# RFID_R1.net
KiCad netlist of a schematic drawn in EAGLE
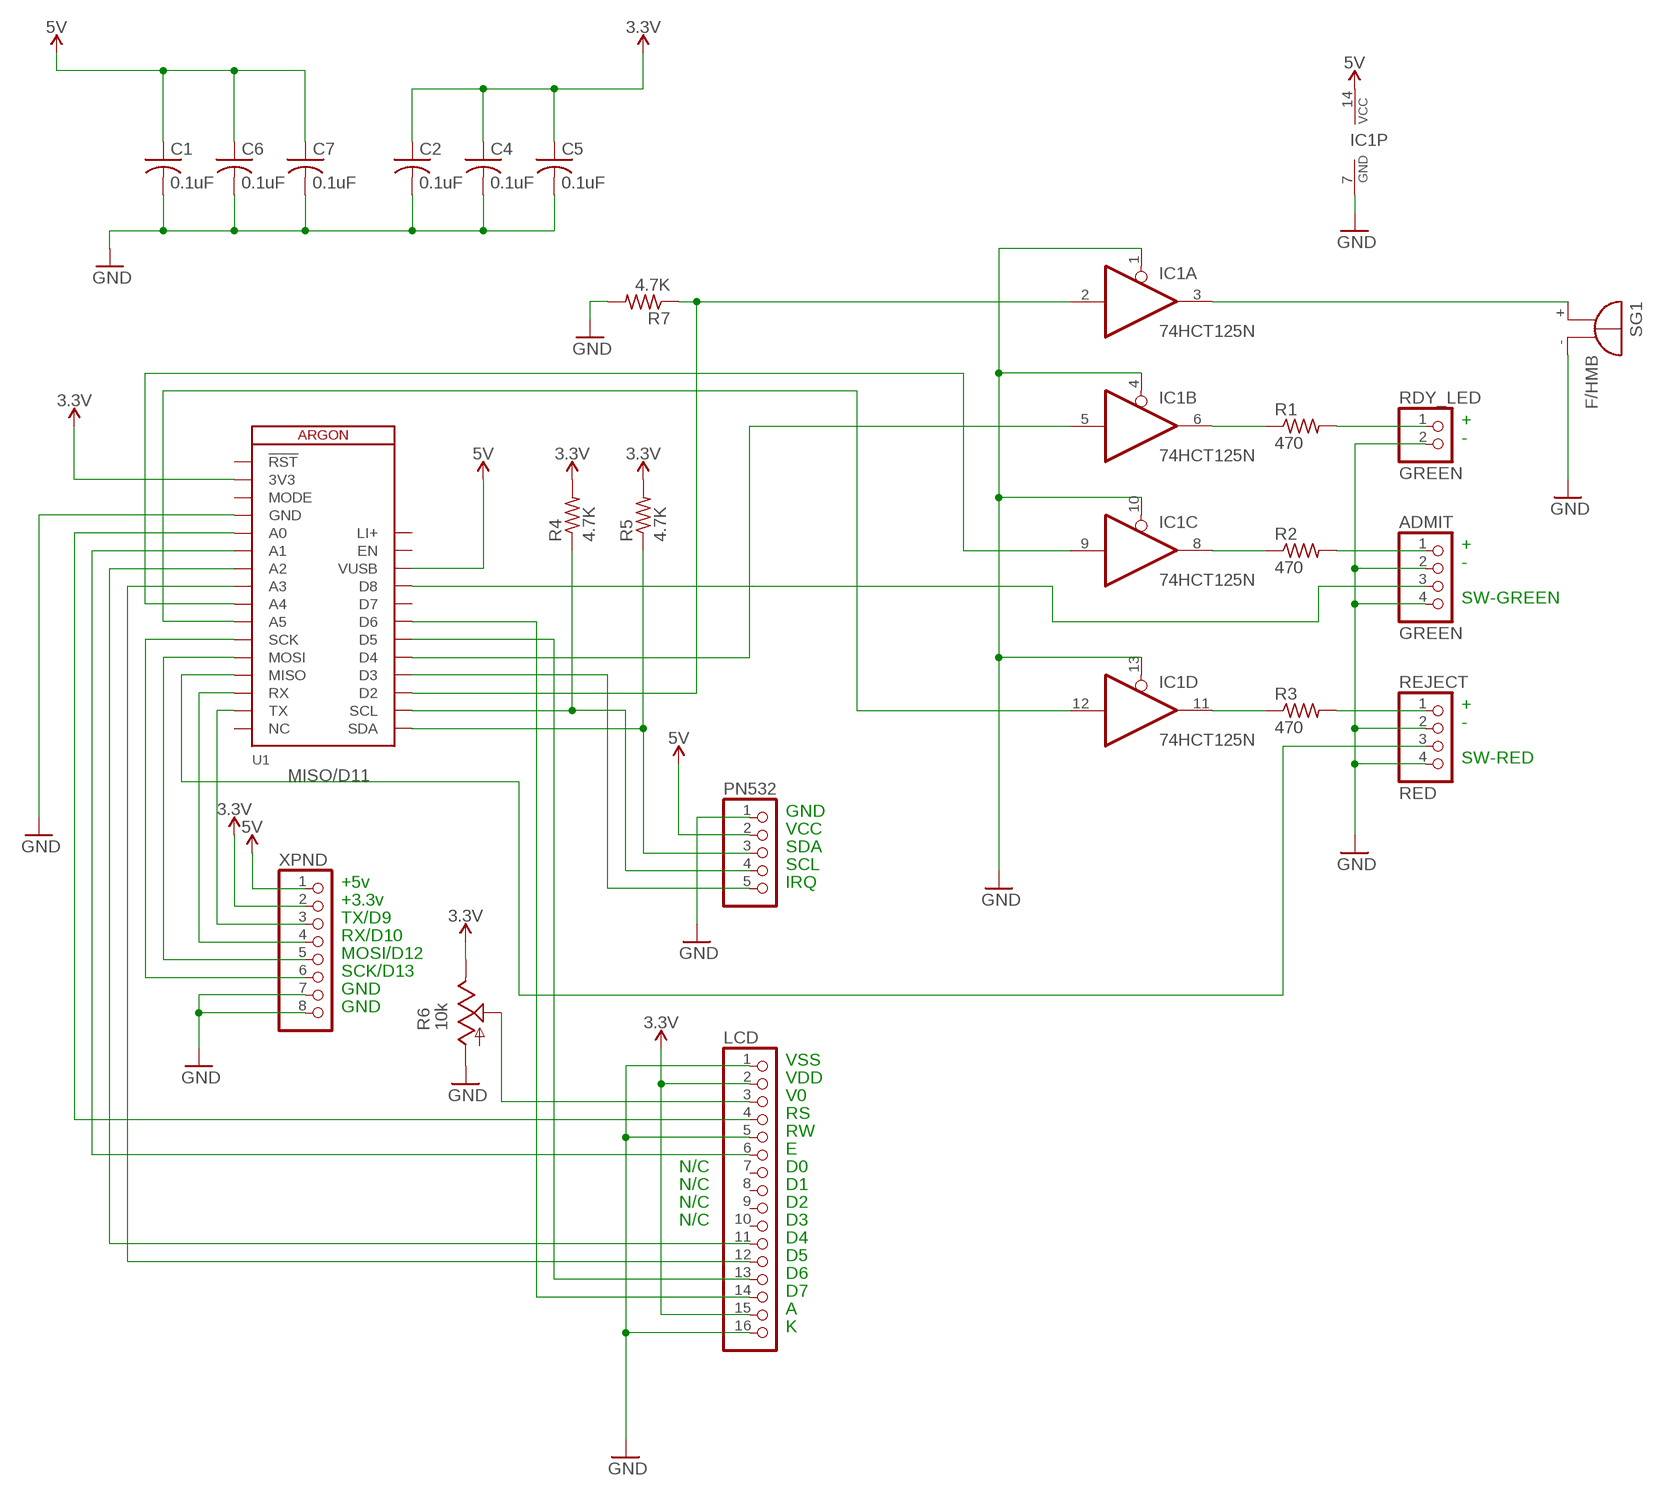
[diagram p0: schematic, sheet 2]

(export (version "E")
  (design (tool "Eeschema 10.0.6"))
  (components
    (comp (ref "ADMIT")
      (value "GREEN")
      (footprint "eagle-import:1X04")
      (libsource (lib "eagle-import") (part "PINHD-1X4"))
    )
    (comp (ref "C1")
      (value "0.1uF")
      (footprint "eagle-import:C025-024X044")
      (libsource (lib "eagle-import") (part "C-US025-024X044"))
    )
    (comp (ref "C2")
      (value "0.1uF")
      (footprint "eagle-import:C025-024X044")
      (libsource (lib "eagle-import") (part "C-US025-024X044"))
    )
    (comp (ref "C4")
      (value "0.1uF")
      (footprint "eagle-import:C025-024X044")
      (libsource (lib "eagle-import") (part "C-US025-024X044"))
    )
    (comp (ref "C5")
      (value "0.1uF")
      (footprint "eagle-import:C025-024X044")
      (libsource (lib "eagle-import") (part "C-US025-024X044"))
    )
    (comp (ref "C6")
      (value "0.1uF")
      (footprint "eagle-import:C025-024X044")
      (libsource (lib "eagle-import") (part "C-US025-024X044"))
    )
    (comp (ref "C7")
      (value "0.1uF")
      (footprint "eagle-import:C025-024X044")
      (libsource (lib "eagle-import") (part "C-US025-024X044"))
    )
    (comp (ref "IC1")
      (value "74HCT125N")
      (footprint "eagle-import:DIL14")
      (libsource (lib "eagle-import") (part "74125NHCT"))
    )
    (comp (ref "LCD")
      (value "PINHD-1X16")
      (footprint "eagle-import:1X16")
      (libsource (lib "eagle-import") (part "PINHD-1X16"))
    )
    (comp (ref "PN532")
      (value "PINHD-1X5")
      (footprint "eagle-import:1X05")
      (libsource (lib "eagle-import") (part "PINHD-1X5"))
    )
    (comp (ref "R1")
      (value "470")
      (footprint "eagle-import:0204_7")
      (libsource (lib "eagle-import") (part "R-US_0204/7"))
    )
    (comp (ref "R2")
      (value "470")
      (footprint "eagle-import:0204_7")
      (libsource (lib "eagle-import") (part "R-US_0204/7"))
    )
    (comp (ref "R3")
      (value "470")
      (footprint "eagle-import:0204_7")
      (libsource (lib "eagle-import") (part "R-US_0204/7"))
    )
    (comp (ref "R4")
      (value "4.7K")
      (footprint "eagle-import:0204_7")
      (libsource (lib "eagle-import") (part "R-US_0204/7"))
    )
    (comp (ref "R5")
      (value "4.7K")
      (footprint "eagle-import:0204_7")
      (libsource (lib "eagle-import") (part "R-US_0204/7"))
    )
    (comp (ref "R6")
      (value "10k")
      (footprint "eagle-import:CT6")
      (libsource (lib "eagle-import") (part "TRIM_US-CT6"))
    )
    (comp (ref "R7")
      (value "4.7K")
      (footprint "eagle-import:0204_7")
      (libsource (lib "eagle-import") (part "R-US_0204/7"))
    )
    (comp (ref "RDY_LED")
      (value "GREEN")
      (footprint "eagle-import:1X02")
      (libsource (lib "eagle-import") (part "PINHD-1X2"))
    )
    (comp (ref "REJECT")
      (value "RED")
      (footprint "eagle-import:1X04")
      (libsource (lib "eagle-import") (part "PINHD-1X4"))
    )
    (comp (ref "SG1")
      (value "F/HMB")
      (footprint "eagle-import:F_HMB")
      (libsource (lib "eagle-import") (part "F/HMB"))
    )
    (comp (ref "U1")
      (value "ARGON")
      (footprint "eagle-import:ARGON")
      (libsource (lib "eagle-import") (part "ARGON"))
    )
    (comp (ref "XPND")
      (value "PINHD-1X8BIG")
      (footprint "eagle-import:1X08-BIG")
      (libsource (lib "eagle-import") (part "PINHD-1X8BIG"))
    )
  )
  (nets
    (net (code "1") (name "3.3V") (class "Default")
      (node (ref "C2") (pin "1") (pinfunction "1_1") (pintype "passive"))
      (node (ref "C4") (pin "1") (pinfunction "1_1") (pintype "passive"))
      (node (ref "C5") (pin "1") (pinfunction "1_1") (pintype "passive"))
      (node (ref "LCD") (pin "15") (pinfunction "15_15") (pintype "passive"))
      (node (ref "LCD") (pin "2") (pinfunction "2_2") (pintype "passive"))
      (node (ref "R4") (pin "2") (pinfunction "2_2") (pintype "passive"))
      (node (ref "R5") (pin "2") (pinfunction "2_2") (pintype "passive"))
      (node (ref "R6") (pin "E") (pinfunction "E_E") (pintype "passive"))
      (node (ref "U1") (pin "2") (pinfunction "3V3_2") (pintype "power_in"))
      (node (ref "XPND") (pin "2") (pinfunction "2_2") (pintype "passive"))
    )
    (net (code "2") (name "5V") (class "Default")
      (node (ref "C1") (pin "1") (pinfunction "1_1") (pintype "passive"))
      (node (ref "C6") (pin "1") (pinfunction "1_1") (pintype "passive"))
      (node (ref "C7") (pin "1") (pinfunction "1_1") (pintype "passive"))
      (node (ref "IC1") (pin "14") (pinfunction "VCC_14") (pintype "power_in"))
      (node (ref "PN532") (pin "2") (pinfunction "2_2") (pintype "passive"))
      (node (ref "U1") (pin "26") (pinfunction "VUSB_26") (pintype "power_in"))
      (node (ref "XPND") (pin "1") (pinfunction "1_1") (pintype "passive"))
    )
    (net (code "3") (name "GND") (class "Default")
      (node (ref "ADMIT") (pin "2") (pinfunction "2_2") (pintype "passive"))
      (node (ref "ADMIT") (pin "4") (pinfunction "4_4") (pintype "passive"))
      (node (ref "C1") (pin "2") (pinfunction "2_2") (pintype "passive"))
      (node (ref "C2") (pin "2") (pinfunction "2_2") (pintype "passive"))
      (node (ref "C4") (pin "2") (pinfunction "2_2") (pintype "passive"))
      (node (ref "C5") (pin "2") (pinfunction "2_2") (pintype "passive"))
      (node (ref "C6") (pin "2") (pinfunction "2_2") (pintype "passive"))
      (node (ref "C7") (pin "2") (pinfunction "2_2") (pintype "passive"))
      (node (ref "IC1") (pin "1") (pinfunction "OE_1") (pintype "input"))
      (node (ref "IC1") (pin "10") (pinfunction "OE_10") (pintype "input"))
      (node (ref "IC1") (pin "13") (pinfunction "OE_13") (pintype "input"))
      (node (ref "IC1") (pin "4") (pinfunction "OE_4") (pintype "input"))
      (node (ref "IC1") (pin "7") (pinfunction "GND_7") (pintype "power_in"))
      (node (ref "LCD") (pin "1") (pinfunction "1_1") (pintype "passive"))
      (node (ref "LCD") (pin "16") (pinfunction "16_16") (pintype "passive"))
      (node (ref "LCD") (pin "5") (pinfunction "5_5") (pintype "passive"))
      (node (ref "PN532") (pin "1") (pinfunction "1_1") (pintype "passive"))
      (node (ref "R6") (pin "A") (pinfunction "A_A") (pintype "passive"))
      (node (ref "R7") (pin "2") (pinfunction "2_2") (pintype "passive"))
      (node (ref "RDY_LED") (pin "2") (pinfunction "2_2") (pintype "passive"))
      (node (ref "REJECT") (pin "2") (pinfunction "2_2") (pintype "passive"))
      (node (ref "REJECT") (pin "4") (pinfunction "4_4") (pintype "passive"))
      (node (ref "SG1") (pin "-") (pinfunction "-_-") (pintype "passive"))
      (node (ref "U1") (pin "4") (pinfunction "GND_4") (pintype "power_in"))
      (node (ref "XPND") (pin "7") (pinfunction "7_7") (pintype "passive"))
      (node (ref "XPND") (pin "8") (pinfunction "8_8") (pintype "passive"))
    )
    (net (code "4") (name "LI+") (class "Default")
      (node (ref "U1") (pin "28") (pinfunction "LI+_28") (pintype "power_in"))
    )
    (net (code "5") (name "MISO{slash}D11") (class "Default")
      (node (ref "REJECT") (pin "3") (pinfunction "3_3") (pintype "passive"))
      (node (ref "U1") (pin "13") (pinfunction "MISO_13") (pintype "bidirectional"))
    )
    (net (code "6") (name "Net-(ADMIT-Pad1)") (class "Default")
      (node (ref "ADMIT") (pin "1") (pinfunction "1_1") (pintype "passive"))
      (node (ref "R2") (pin "2") (pinfunction "2_2") (pintype "passive"))
    )
    (net (code "7") (name "Net-(IC1A-I)") (class "Default")
      (node (ref "IC1") (pin "2") (pinfunction "I_2") (pintype "input"))
      (node (ref "R7") (pin "1") (pinfunction "1_1") (pintype "passive"))
      (node (ref "U1") (pin "19") (pinfunction "D2_19") (pintype "bidirectional"))
    )
    (net (code "8") (name "Net-(IC1A-O)") (class "Default")
      (node (ref "IC1") (pin "3") (pinfunction "O_3") (pintype "tri_state"))
      (node (ref "SG1") (pin "+") (pinfunction "+_+") (pintype "passive"))
    )
    (net (code "9") (name "Net-(IC1B-I)") (class "Default")
      (node (ref "IC1") (pin "5") (pinfunction "I_5") (pintype "input"))
      (node (ref "U1") (pin "21") (pinfunction "D4_21") (pintype "bidirectional"))
    )
    (net (code "10") (name "Net-(IC1B-O)") (class "Default")
      (node (ref "IC1") (pin "6") (pinfunction "O_6") (pintype "tri_state"))
      (node (ref "R1") (pin "1") (pinfunction "1_1") (pintype "passive"))
    )
    (net (code "11") (name "Net-(IC1C-I)") (class "Default")
      (node (ref "IC1") (pin "9") (pinfunction "I_9") (pintype "input"))
      (node (ref "U1") (pin "9") (pinfunction "A4_9") (pintype "bidirectional"))
    )
    (net (code "12") (name "Net-(IC1C-O)") (class "Default")
      (node (ref "IC1") (pin "8") (pinfunction "O_8") (pintype "tri_state"))
      (node (ref "R2") (pin "1") (pinfunction "1_1") (pintype "passive"))
    )
    (net (code "13") (name "Net-(IC1D-I)") (class "Default")
      (node (ref "IC1") (pin "12") (pinfunction "I_12") (pintype "input"))
      (node (ref "U1") (pin "10") (pinfunction "A5_10") (pintype "bidirectional"))
    )
    (net (code "14") (name "Net-(IC1D-O)") (class "Default")
      (node (ref "IC1") (pin "11") (pinfunction "O_11") (pintype "tri_state"))
      (node (ref "R3") (pin "1") (pinfunction "1_1") (pintype "passive"))
    )
    (net (code "15") (name "Net-(LCD-Pad3)") (class "Default")
      (node (ref "LCD") (pin "3") (pinfunction "3_3") (pintype "passive"))
      (node (ref "R6") (pin "S") (pinfunction "S_S") (pintype "passive"))
    )
    (net (code "16") (name "Net-(R1-Pad2)") (class "Default")
      (node (ref "R1") (pin "2") (pinfunction "2_2") (pintype "passive"))
      (node (ref "RDY_LED") (pin "1") (pinfunction "1_1") (pintype "passive"))
    )
    (net (code "17") (name "Net-(R3-Pad2)") (class "Default")
      (node (ref "R3") (pin "2") (pinfunction "2_2") (pintype "passive"))
      (node (ref "REJECT") (pin "1") (pinfunction "1_1") (pintype "passive"))
    )
    (net (code "18") (name "Net-(U1-A0)") (class "Default")
      (node (ref "LCD") (pin "4") (pinfunction "4_4") (pintype "passive"))
      (node (ref "U1") (pin "5") (pinfunction "A0_5") (pintype "bidirectional"))
    )
    (net (code "19") (name "Net-(U1-A1)") (class "Default")
      (node (ref "LCD") (pin "6") (pinfunction "6_6") (pintype "passive"))
      (node (ref "U1") (pin "6") (pinfunction "A1_6") (pintype "bidirectional"))
    )
    (net (code "20") (name "Net-(U1-A2)") (class "Default")
      (node (ref "LCD") (pin "11") (pinfunction "11_11") (pintype "passive"))
      (node (ref "U1") (pin "7") (pinfunction "A2_7") (pintype "bidirectional"))
    )
    (net (code "21") (name "Net-(U1-A3)") (class "Default")
      (node (ref "LCD") (pin "12") (pinfunction "12_12") (pintype "passive"))
      (node (ref "U1") (pin "8") (pinfunction "A3_8") (pintype "bidirectional"))
    )
    (net (code "22") (name "Net-(U1-D3)") (class "Default")
      (node (ref "PN532") (pin "5") (pinfunction "5_5") (pintype "passive"))
      (node (ref "U1") (pin "20") (pinfunction "D3_20") (pintype "bidirectional"))
    )
    (net (code "23") (name "Net-(U1-D5)") (class "Default")
      (node (ref "LCD") (pin "13") (pinfunction "13_13") (pintype "passive"))
      (node (ref "U1") (pin "22") (pinfunction "D5_22") (pintype "bidirectional"))
    )
    (net (code "24") (name "Net-(U1-D6)") (class "Default")
      (node (ref "LCD") (pin "14") (pinfunction "14_14") (pintype "passive"))
      (node (ref "U1") (pin "23") (pinfunction "D6_23") (pintype "bidirectional"))
    )
    (net (code "25") (name "Net-(U1-D8)") (class "Default")
      (node (ref "ADMIT") (pin "3") (pinfunction "3_3") (pintype "passive"))
      (node (ref "U1") (pin "25") (pinfunction "D8_25") (pintype "bidirectional"))
    )
    (net (code "26") (name "Net-(U1-MOSI)") (class "Default")
      (node (ref "U1") (pin "12") (pinfunction "MOSI_12") (pintype "bidirectional"))
      (node (ref "XPND") (pin "5") (pinfunction "5_5") (pintype "passive"))
    )
    (net (code "27") (name "Net-(U1-RX)") (class "Default")
      (node (ref "U1") (pin "14") (pinfunction "RX_14") (pintype "bidirectional"))
      (node (ref "XPND") (pin "4") (pinfunction "4_4") (pintype "passive"))
    )
    (net (code "28") (name "Net-(U1-SCK)") (class "Default")
      (node (ref "U1") (pin "11") (pinfunction "SCK_11") (pintype "bidirectional"))
      (node (ref "XPND") (pin "6") (pinfunction "6_6") (pintype "passive"))
    )
    (net (code "29") (name "Net-(U1-SCL)") (class "Default")
      (node (ref "PN532") (pin "4") (pinfunction "4_4") (pintype "passive"))
      (node (ref "R4") (pin "1") (pinfunction "1_1") (pintype "passive"))
      (node (ref "U1") (pin "18") (pinfunction "SCL_18") (pintype "bidirectional"))
    )
    (net (code "30") (name "Net-(U1-SDA)") (class "Default")
      (node (ref "PN532") (pin "3") (pinfunction "3_3") (pintype "passive"))
      (node (ref "R5") (pin "1") (pinfunction "1_1") (pintype "passive"))
      (node (ref "U1") (pin "17") (pinfunction "SDA_17") (pintype "bidirectional"))
    )
    (net (code "31") (name "Net-(U1-TX)") (class "Default")
      (node (ref "U1") (pin "15") (pinfunction "TX_15") (pintype "bidirectional"))
      (node (ref "XPND") (pin "3") (pinfunction "3_3") (pintype "passive"))
    )
    (net (code "32") (name "unconnected-(LCD-Pad7)") (class "Default")
      (node (ref "LCD") (pin "7") (pinfunction "7_7") (pintype "passive"))
    )
    (net (code "33") (name "unconnected-(LCD-Pad8)") (class "Default")
      (node (ref "LCD") (pin "8") (pinfunction "8_8") (pintype "passive"))
    )
    (net (code "34") (name "unconnected-(LCD-Pad9)") (class "Default")
      (node (ref "LCD") (pin "9") (pinfunction "9_9") (pintype "passive"))
    )
    (net (code "35") (name "unconnected-(LCD-Pad10)") (class "Default")
      (node (ref "LCD") (pin "10") (pinfunction "10_10") (pintype "passive"))
    )
    (net (code "36") (name "unconnected-(U1-D7-Pad24)") (class "Default")
      (node (ref "U1") (pin "24") (pinfunction "D7_24") (pintype "bidirectional"))
    )
    (net (code "37") (name "unconnected-(U1-EN-Pad27)") (class "Default")
      (node (ref "U1") (pin "27") (pinfunction "EN_27") (pintype "input"))
    )
    (net (code "38") (name "unconnected-(U1-MODE-Pad3)") (class "Default")
      (node (ref "U1") (pin "3") (pinfunction "MODE_3") (pintype "bidirectional"))
    )
    (net (code "39") (name "unconnected-(U1-NC-Pad16)") (class "Default")
      (node (ref "U1") (pin "16") (pinfunction "NC_16") (pintype "bidirectional"))
    )
    (net (code "40") (name "unconnected-(U1-~{RST}-Pad1)") (class "Default")
      (node (ref "U1") (pin "1") (pinfunction "~{RST}_1") (pintype "input"))
    )
  )
)
